# S123X.net
KiCad netlist of a schematic drawn in EAGLE
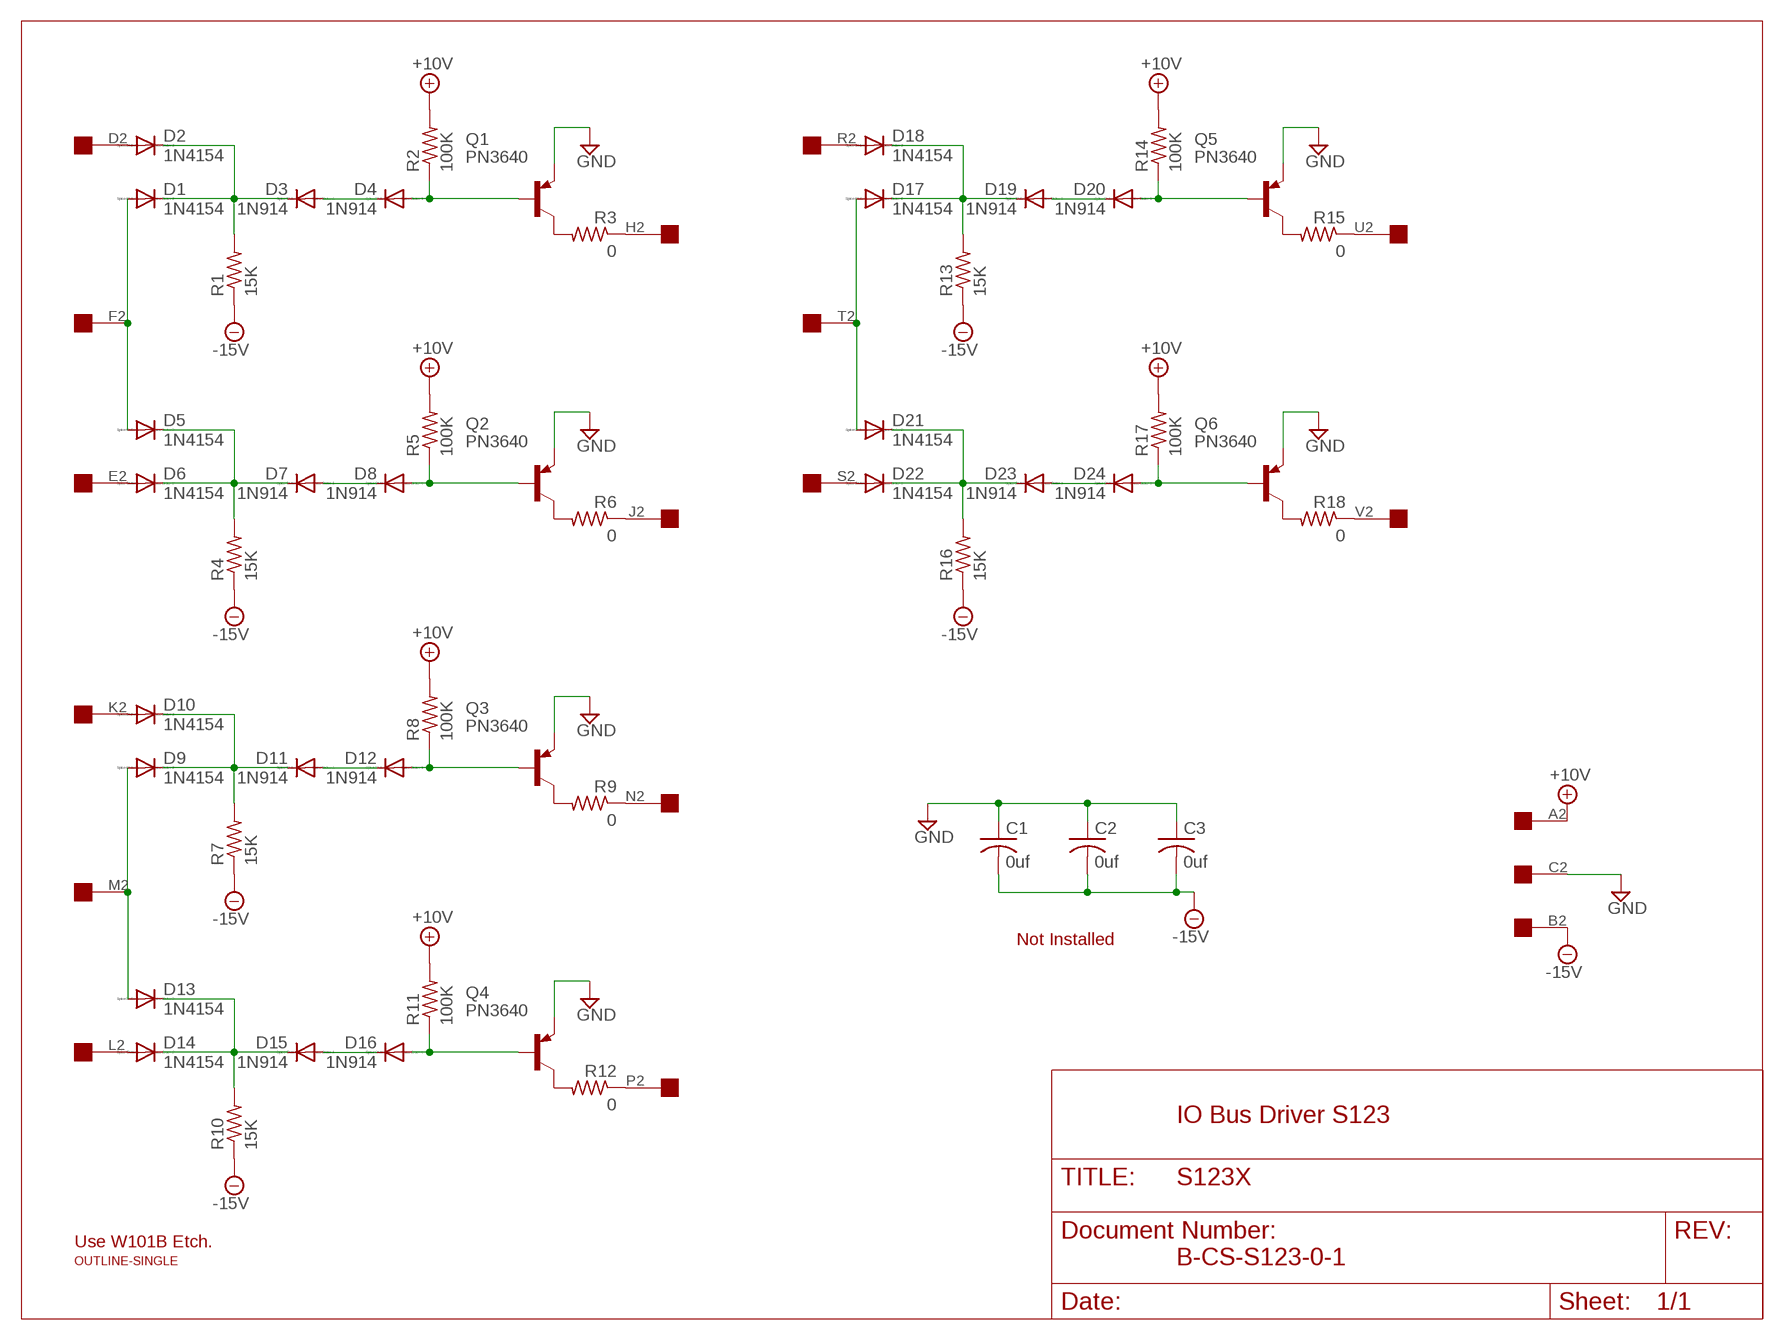
[diagram p0: schematic, sheet 1]

(export (version "E")
  (design (tool "Eeschema 10.0.6"))
  (components
    (comp (ref "C1")
      (value "0uf")
      (footprint "eagle-import:C050-025X075")
      (libsource (lib "eagle-import") (part "C-US050-025X075"))
    )
    (comp (ref "C2")
      (value "0uf")
      (footprint "eagle-import:C050-025X075")
      (libsource (lib "eagle-import") (part "C-US050-025X075"))
    )
    (comp (ref "C3")
      (value "0uf")
      (footprint "eagle-import:C050-025X075")
      (libsource (lib "eagle-import") (part "C-US050-025X075"))
    )
    (comp (ref "D1")
      (value "1N4154")
      (footprint "eagle-import:DO35-10")
      (libsource (lib "eagle-import") (part "1N4148DO35-10"))
    )
    (comp (ref "D2")
      (value "1N4154")
      (footprint "eagle-import:DO35-10")
      (libsource (lib "eagle-import") (part "1N4148DO35-10"))
    )
    (comp (ref "D3")
      (value "1N914")
      (footprint "eagle-import:DO35-10")
      (libsource (lib "eagle-import") (part "1N4148DO35-10"))
    )
    (comp (ref "D4")
      (value "1N914")
      (footprint "eagle-import:DO35-10")
      (libsource (lib "eagle-import") (part "1N4148DO35-10"))
    )
    (comp (ref "D5")
      (value "1N4154")
      (footprint "eagle-import:DO35-10")
      (libsource (lib "eagle-import") (part "1N4148DO35-10"))
    )
    (comp (ref "D6")
      (value "1N4154")
      (footprint "eagle-import:DO35-10")
      (libsource (lib "eagle-import") (part "1N4148DO35-10"))
    )
    (comp (ref "D7")
      (value "1N914")
      (footprint "eagle-import:DO35-10")
      (libsource (lib "eagle-import") (part "1N4148DO35-10"))
    )
    (comp (ref "D8")
      (value "1N914")
      (footprint "eagle-import:DO35-10")
      (libsource (lib "eagle-import") (part "1N4148DO35-10"))
    )
    (comp (ref "D9")
      (value "1N4154")
      (footprint "eagle-import:DO35-10")
      (libsource (lib "eagle-import") (part "1N4148DO35-10"))
    )
    (comp (ref "D10")
      (value "1N4154")
      (footprint "eagle-import:DO35-10")
      (libsource (lib "eagle-import") (part "1N4148DO35-10"))
    )
    (comp (ref "D11")
      (value "1N914")
      (footprint "eagle-import:DO35-10")
      (libsource (lib "eagle-import") (part "1N4148DO35-10"))
    )
    (comp (ref "D12")
      (value "1N914")
      (footprint "eagle-import:DO35-10")
      (libsource (lib "eagle-import") (part "1N4148DO35-10"))
    )
    (comp (ref "D13")
      (value "1N4154")
      (footprint "eagle-import:DO35-10")
      (libsource (lib "eagle-import") (part "1N4148DO35-10"))
    )
    (comp (ref "D14")
      (value "1N4154")
      (footprint "eagle-import:DO35-10")
      (libsource (lib "eagle-import") (part "1N4148DO35-10"))
    )
    (comp (ref "D15")
      (value "1N914")
      (footprint "eagle-import:DO35-10")
      (libsource (lib "eagle-import") (part "1N4148DO35-10"))
    )
    (comp (ref "D16")
      (value "1N914")
      (footprint "eagle-import:DO35-10")
      (libsource (lib "eagle-import") (part "1N4148DO35-10"))
    )
    (comp (ref "D17")
      (value "1N4154")
      (footprint "eagle-import:DO35-10")
      (libsource (lib "eagle-import") (part "1N4148DO35-10"))
    )
    (comp (ref "D18")
      (value "1N4154")
      (footprint "eagle-import:DO35-10")
      (libsource (lib "eagle-import") (part "1N4148DO35-10"))
    )
    (comp (ref "D19")
      (value "1N914")
      (footprint "eagle-import:DO35-10")
      (libsource (lib "eagle-import") (part "1N4148DO35-10"))
    )
    (comp (ref "D20")
      (value "1N914")
      (footprint "eagle-import:DO35-10")
      (libsource (lib "eagle-import") (part "1N4148DO35-10"))
    )
    (comp (ref "D21")
      (value "1N4154")
      (footprint "eagle-import:DO35-10")
      (libsource (lib "eagle-import") (part "1N4148DO35-10"))
    )
    (comp (ref "D22")
      (value "1N4154")
      (footprint "eagle-import:DO35-10")
      (libsource (lib "eagle-import") (part "1N4148DO35-10"))
    )
    (comp (ref "D23")
      (value "1N914")
      (footprint "eagle-import:DO35-10")
      (libsource (lib "eagle-import") (part "1N4148DO35-10"))
    )
    (comp (ref "D24")
      (value "1N914")
      (footprint "eagle-import:DO35-10")
      (libsource (lib "eagle-import") (part "1N4148DO35-10"))
    )
    (comp (ref "Q1")
      (value "PN3640")
      (footprint "eagle-import:TO39")
      (libsource (lib "eagle-import") (part "2N3637"))
    )
    (comp (ref "Q2")
      (value "PN3640")
      (footprint "eagle-import:TO39")
      (libsource (lib "eagle-import") (part "2N3637"))
    )
    (comp (ref "Q3")
      (value "PN3640")
      (footprint "eagle-import:TO39")
      (libsource (lib "eagle-import") (part "2N3637"))
    )
    (comp (ref "Q4")
      (value "PN3640")
      (footprint "eagle-import:TO39")
      (libsource (lib "eagle-import") (part "2N3637"))
    )
    (comp (ref "Q5")
      (value "PN3640")
      (footprint "eagle-import:TO39")
      (libsource (lib "eagle-import") (part "2N3637"))
    )
    (comp (ref "Q6")
      (value "PN3640")
      (footprint "eagle-import:TO39")
      (libsource (lib "eagle-import") (part "2N3637"))
    )
    (comp (ref "R1")
      (value "15K")
      (footprint "eagle-import:0207_10")
      (libsource (lib "eagle-import") (part "R-US_0207/10"))
    )
    (comp (ref "R2")
      (value "100K")
      (footprint "eagle-import:0207_10")
      (libsource (lib "eagle-import") (part "R-US_0207/10"))
    )
    (comp (ref "R3")
      (value "0")
      (footprint "eagle-import:0207_10")
      (libsource (lib "eagle-import") (part "R-US_0207/10"))
    )
    (comp (ref "R4")
      (value "15K")
      (footprint "eagle-import:0207_10")
      (libsource (lib "eagle-import") (part "R-US_0207/10"))
    )
    (comp (ref "R5")
      (value "100K")
      (footprint "eagle-import:0207_10")
      (libsource (lib "eagle-import") (part "R-US_0207/10"))
    )
    (comp (ref "R6")
      (value "0")
      (footprint "eagle-import:0207_10")
      (libsource (lib "eagle-import") (part "R-US_0207/10"))
    )
    (comp (ref "R7")
      (value "15K")
      (footprint "eagle-import:0207_10")
      (libsource (lib "eagle-import") (part "R-US_0207/10"))
    )
    (comp (ref "R8")
      (value "100K")
      (footprint "eagle-import:0207_10")
      (libsource (lib "eagle-import") (part "R-US_0207/10"))
    )
    (comp (ref "R9")
      (value "0")
      (footprint "eagle-import:0207_10")
      (libsource (lib "eagle-import") (part "R-US_0207/10"))
    )
    (comp (ref "R10")
      (value "15K")
      (footprint "eagle-import:0207_10")
      (libsource (lib "eagle-import") (part "R-US_0207/10"))
    )
    (comp (ref "R11")
      (value "100K")
      (footprint "eagle-import:0207_10")
      (libsource (lib "eagle-import") (part "R-US_0207/10"))
    )
    (comp (ref "R12")
      (value "0")
      (footprint "eagle-import:0207_10")
      (libsource (lib "eagle-import") (part "R-US_0207/10"))
    )
    (comp (ref "R13")
      (value "15K")
      (footprint "eagle-import:0207_10")
      (libsource (lib "eagle-import") (part "R-US_0207/10"))
    )
    (comp (ref "R14")
      (value "100K")
      (footprint "eagle-import:0207_10")
      (libsource (lib "eagle-import") (part "R-US_0207/10"))
    )
    (comp (ref "R15")
      (value "0")
      (footprint "eagle-import:0207_10")
      (libsource (lib "eagle-import") (part "R-US_0207/10"))
    )
    (comp (ref "R16")
      (value "15K")
      (footprint "eagle-import:0207_10")
      (libsource (lib "eagle-import") (part "R-US_0207/10"))
    )
    (comp (ref "R17")
      (value "100K")
      (footprint "eagle-import:0207_10")
      (libsource (lib "eagle-import") (part "R-US_0207/10"))
    )
    (comp (ref "R18")
      (value "0")
      (footprint "eagle-import:0207_10")
      (libsource (lib "eagle-import") (part "R-US_0207/10"))
    )
    (comp (ref "U$1")
      (value "OUTLINE-SINGLE")
      (footprint "eagle-import:SINGLE")
      (libsource (lib "eagle-import") (part "OUTLINE-SINGLE"))
    )
    (comp (ref "U$2")
      (value "EDGE-1")
      (footprint "eagle-import:EDGE-CON1")
      (libsource (lib "eagle-import") (part "EDGE-1"))
    )
  )
  (nets
    (net (code "1") (name "+10V") (class "Default")
      (node (ref "R11") (pin "2") (pinfunction "2_2") (pintype "passive"))
      (node (ref "R14") (pin "2") (pinfunction "2_2") (pintype "passive"))
      (node (ref "R17") (pin "2") (pinfunction "2_2") (pintype "passive"))
      (node (ref "R2") (pin "2") (pinfunction "2_2") (pintype "passive"))
      (node (ref "R5") (pin "2") (pinfunction "2_2") (pintype "passive"))
      (node (ref "R8") (pin "2") (pinfunction "2_2") (pintype "passive"))
      (node (ref "U$2") (pin "A2") (pinfunction "1_A2") (pintype "bidirectional"))
    )
    (net (code "2") (name "-15V") (class "Default")
      (node (ref "C1") (pin "2") (pinfunction "2_2") (pintype "passive"))
      (node (ref "C2") (pin "2") (pinfunction "2_2") (pintype "passive"))
      (node (ref "C3") (pin "2") (pinfunction "2_2") (pintype "passive"))
      (node (ref "R1") (pin "1") (pinfunction "1_1") (pintype "passive"))
      (node (ref "R10") (pin "1") (pinfunction "1_1") (pintype "passive"))
      (node (ref "R13") (pin "1") (pinfunction "1_1") (pintype "passive"))
      (node (ref "R16") (pin "1") (pinfunction "1_1") (pintype "passive"))
      (node (ref "R4") (pin "1") (pinfunction "1_1") (pintype "passive"))
      (node (ref "R7") (pin "1") (pinfunction "1_1") (pintype "passive"))
      (node (ref "U$2") (pin "B2") (pinfunction "1_B2") (pintype "bidirectional"))
    )
    (net (code "3") (name "GND") (class "Default")
      (node (ref "C1") (pin "1") (pinfunction "1_1") (pintype "passive"))
      (node (ref "C2") (pin "1") (pinfunction "1_1") (pintype "passive"))
      (node (ref "C3") (pin "1") (pinfunction "1_1") (pintype "passive"))
      (node (ref "Q1") (pin "1") (pinfunction "E_1") (pintype "passive"))
      (node (ref "Q2") (pin "1") (pinfunction "E_1") (pintype "passive"))
      (node (ref "Q3") (pin "1") (pinfunction "E_1") (pintype "passive"))
      (node (ref "Q4") (pin "1") (pinfunction "E_1") (pintype "passive"))
      (node (ref "Q5") (pin "1") (pinfunction "E_1") (pintype "passive"))
      (node (ref "Q6") (pin "1") (pinfunction "E_1") (pintype "passive"))
      (node (ref "U$2") (pin "C2") (pinfunction "1_C2") (pintype "bidirectional"))
    )
    (net (code "4") (name "Net-(D1-PadC)") (class "Default")
      (node (ref "D1") (pin "C") (pinfunction "C_C") (pintype "passive"))
      (node (ref "D2") (pin "C") (pinfunction "C_C") (pintype "passive"))
      (node (ref "D3") (pin "C") (pinfunction "C_C") (pintype "passive"))
      (node (ref "R1") (pin "2") (pinfunction "2_2") (pintype "passive"))
    )
    (net (code "5") (name "Net-(D3-PadA)") (class "Default")
      (node (ref "D3") (pin "A") (pinfunction "A_A") (pintype "passive"))
      (node (ref "D4") (pin "C") (pinfunction "C_C") (pintype "passive"))
    )
    (net (code "6") (name "Net-(D5-PadC)") (class "Default")
      (node (ref "D5") (pin "C") (pinfunction "C_C") (pintype "passive"))
      (node (ref "D6") (pin "C") (pinfunction "C_C") (pintype "passive"))
      (node (ref "D7") (pin "C") (pinfunction "C_C") (pintype "passive"))
      (node (ref "R4") (pin "2") (pinfunction "2_2") (pintype "passive"))
    )
    (net (code "7") (name "Net-(D7-PadA)") (class "Default")
      (node (ref "D7") (pin "A") (pinfunction "A_A") (pintype "passive"))
      (node (ref "D8") (pin "C") (pinfunction "C_C") (pintype "passive"))
    )
    (net (code "8") (name "Net-(D10-PadC)") (class "Default")
      (node (ref "D10") (pin "C") (pinfunction "C_C") (pintype "passive"))
      (node (ref "D11") (pin "C") (pinfunction "C_C") (pintype "passive"))
      (node (ref "D9") (pin "C") (pinfunction "C_C") (pintype "passive"))
      (node (ref "R7") (pin "2") (pinfunction "2_2") (pintype "passive"))
    )
    (net (code "9") (name "Net-(D11-PadA)") (class "Default")
      (node (ref "D11") (pin "A") (pinfunction "A_A") (pintype "passive"))
      (node (ref "D12") (pin "C") (pinfunction "C_C") (pintype "passive"))
    )
    (net (code "10") (name "Net-(D13-PadC)") (class "Default")
      (node (ref "D13") (pin "C") (pinfunction "C_C") (pintype "passive"))
      (node (ref "D14") (pin "C") (pinfunction "C_C") (pintype "passive"))
      (node (ref "D15") (pin "C") (pinfunction "C_C") (pintype "passive"))
      (node (ref "R10") (pin "2") (pinfunction "2_2") (pintype "passive"))
    )
    (net (code "11") (name "Net-(D15-PadA)") (class "Default")
      (node (ref "D15") (pin "A") (pinfunction "A_A") (pintype "passive"))
      (node (ref "D16") (pin "C") (pinfunction "C_C") (pintype "passive"))
    )
    (net (code "12") (name "Net-(D17-PadC)") (class "Default")
      (node (ref "D17") (pin "C") (pinfunction "C_C") (pintype "passive"))
      (node (ref "D18") (pin "C") (pinfunction "C_C") (pintype "passive"))
      (node (ref "D19") (pin "C") (pinfunction "C_C") (pintype "passive"))
      (node (ref "R13") (pin "2") (pinfunction "2_2") (pintype "passive"))
    )
    (net (code "13") (name "Net-(D19-PadA)") (class "Default")
      (node (ref "D19") (pin "A") (pinfunction "A_A") (pintype "passive"))
      (node (ref "D20") (pin "C") (pinfunction "C_C") (pintype "passive"))
    )
    (net (code "14") (name "Net-(D21-PadC)") (class "Default")
      (node (ref "D21") (pin "C") (pinfunction "C_C") (pintype "passive"))
      (node (ref "D22") (pin "C") (pinfunction "C_C") (pintype "passive"))
      (node (ref "D23") (pin "C") (pinfunction "C_C") (pintype "passive"))
      (node (ref "R16") (pin "2") (pinfunction "2_2") (pintype "passive"))
    )
    (net (code "15") (name "Net-(D23-PadA)") (class "Default")
      (node (ref "D23") (pin "A") (pinfunction "A_A") (pintype "passive"))
      (node (ref "D24") (pin "C") (pinfunction "C_C") (pintype "passive"))
    )
    (net (code "16") (name "Net-(Q1-B)") (class "Default")
      (node (ref "D4") (pin "A") (pinfunction "A_A") (pintype "passive"))
      (node (ref "Q1") (pin "2") (pinfunction "B_2") (pintype "passive"))
      (node (ref "R2") (pin "1") (pinfunction "1_1") (pintype "passive"))
    )
    (net (code "17") (name "Net-(Q1-C)") (class "Default")
      (node (ref "Q1") (pin "3") (pinfunction "C_3") (pintype "passive"))
      (node (ref "R3") (pin "2") (pinfunction "2_2") (pintype "passive"))
    )
    (net (code "18") (name "Net-(Q2-B)") (class "Default")
      (node (ref "D8") (pin "A") (pinfunction "A_A") (pintype "passive"))
      (node (ref "Q2") (pin "2") (pinfunction "B_2") (pintype "passive"))
      (node (ref "R5") (pin "1") (pinfunction "1_1") (pintype "passive"))
    )
    (net (code "19") (name "Net-(Q2-C)") (class "Default")
      (node (ref "Q2") (pin "3") (pinfunction "C_3") (pintype "passive"))
      (node (ref "R6") (pin "2") (pinfunction "2_2") (pintype "passive"))
    )
    (net (code "20") (name "Net-(Q3-B)") (class "Default")
      (node (ref "D12") (pin "A") (pinfunction "A_A") (pintype "passive"))
      (node (ref "Q3") (pin "2") (pinfunction "B_2") (pintype "passive"))
      (node (ref "R8") (pin "1") (pinfunction "1_1") (pintype "passive"))
    )
    (net (code "21") (name "Net-(Q3-C)") (class "Default")
      (node (ref "Q3") (pin "3") (pinfunction "C_3") (pintype "passive"))
      (node (ref "R9") (pin "2") (pinfunction "2_2") (pintype "passive"))
    )
    (net (code "22") (name "Net-(Q4-B)") (class "Default")
      (node (ref "D16") (pin "A") (pinfunction "A_A") (pintype "passive"))
      (node (ref "Q4") (pin "2") (pinfunction "B_2") (pintype "passive"))
      (node (ref "R11") (pin "1") (pinfunction "1_1") (pintype "passive"))
    )
    (net (code "23") (name "Net-(Q4-C)") (class "Default")
      (node (ref "Q4") (pin "3") (pinfunction "C_3") (pintype "passive"))
      (node (ref "R12") (pin "2") (pinfunction "2_2") (pintype "passive"))
    )
    (net (code "24") (name "Net-(Q5-B)") (class "Default")
      (node (ref "D20") (pin "A") (pinfunction "A_A") (pintype "passive"))
      (node (ref "Q5") (pin "2") (pinfunction "B_2") (pintype "passive"))
      (node (ref "R14") (pin "1") (pinfunction "1_1") (pintype "passive"))
    )
    (net (code "25") (name "Net-(Q5-C)") (class "Default")
      (node (ref "Q5") (pin "3") (pinfunction "C_3") (pintype "passive"))
      (node (ref "R15") (pin "2") (pinfunction "2_2") (pintype "passive"))
    )
    (net (code "26") (name "Net-(Q6-B)") (class "Default")
      (node (ref "D24") (pin "A") (pinfunction "A_A") (pintype "passive"))
      (node (ref "Q6") (pin "2") (pinfunction "B_2") (pintype "passive"))
      (node (ref "R17") (pin "1") (pinfunction "1_1") (pintype "passive"))
    )
    (net (code "27") (name "Net-(Q6-C)") (class "Default")
      (node (ref "Q6") (pin "3") (pinfunction "C_3") (pintype "passive"))
      (node (ref "R18") (pin "2") (pinfunction "2_2") (pintype "passive"))
    )
    (net (code "28") (name "Net-(U$2D-1)") (class "Default")
      (node (ref "D2") (pin "A") (pinfunction "A_A") (pintype "passive"))
      (node (ref "U$2") (pin "D2") (pinfunction "1_D2") (pintype "bidirectional"))
    )
    (net (code "29") (name "Net-(U$2E-1)") (class "Default")
      (node (ref "D6") (pin "A") (pinfunction "A_A") (pintype "passive"))
      (node (ref "U$2") (pin "E2") (pinfunction "1_E2") (pintype "bidirectional"))
    )
    (net (code "30") (name "Net-(U$2F-1)") (class "Default")
      (node (ref "D1") (pin "A") (pinfunction "A_A") (pintype "passive"))
      (node (ref "D5") (pin "A") (pinfunction "A_A") (pintype "passive"))
      (node (ref "U$2") (pin "F2") (pinfunction "1_F2") (pintype "bidirectional"))
    )
    (net (code "31") (name "Net-(U$2G-1)") (class "Default")
      (node (ref "R3") (pin "1") (pinfunction "1_1") (pintype "passive"))
      (node (ref "U$2") (pin "H2") (pinfunction "1_H2") (pintype "bidirectional"))
    )
    (net (code "32") (name "Net-(U$2H-1)") (class "Default")
      (node (ref "R6") (pin "1") (pinfunction "1_1") (pintype "passive"))
      (node (ref "U$2") (pin "J2") (pinfunction "1_J2") (pintype "bidirectional"))
    )
    (net (code "33") (name "Net-(U$2I-1)") (class "Default")
      (node (ref "D10") (pin "A") (pinfunction "A_A") (pintype "passive"))
      (node (ref "U$2") (pin "K2") (pinfunction "1_K2") (pintype "bidirectional"))
    )
    (net (code "34") (name "Net-(U$2J-1)") (class "Default")
      (node (ref "D14") (pin "A") (pinfunction "A_A") (pintype "passive"))
      (node (ref "U$2") (pin "L2") (pinfunction "1_L2") (pintype "bidirectional"))
    )
    (net (code "35") (name "Net-(U$2K-1)") (class "Default")
      (node (ref "D13") (pin "A") (pinfunction "A_A") (pintype "passive"))
      (node (ref "D9") (pin "A") (pinfunction "A_A") (pintype "passive"))
      (node (ref "U$2") (pin "M2") (pinfunction "1_M2") (pintype "bidirectional"))
    )
    (net (code "36") (name "Net-(U$2L-1)") (class "Default")
      (node (ref "R9") (pin "1") (pinfunction "1_1") (pintype "passive"))
      (node (ref "U$2") (pin "N2") (pinfunction "1_N2") (pintype "bidirectional"))
    )
    (net (code "37") (name "Net-(U$2M-1)") (class "Default")
      (node (ref "R12") (pin "1") (pinfunction "1_1") (pintype "passive"))
      (node (ref "U$2") (pin "P2") (pinfunction "1_P2") (pintype "bidirectional"))
    )
    (net (code "38") (name "Net-(U$2N-1)") (class "Default")
      (node (ref "D18") (pin "A") (pinfunction "A_A") (pintype "passive"))
      (node (ref "U$2") (pin "R2") (pinfunction "1_R2") (pintype "bidirectional"))
    )
    (net (code "39") (name "Net-(U$2O-1)") (class "Default")
      (node (ref "D22") (pin "A") (pinfunction "A_A") (pintype "passive"))
      (node (ref "U$2") (pin "S2") (pinfunction "1_S2") (pintype "bidirectional"))
    )
    (net (code "40") (name "Net-(U$2P-1)") (class "Default")
      (node (ref "D17") (pin "A") (pinfunction "A_A") (pintype "passive"))
      (node (ref "D21") (pin "A") (pinfunction "A_A") (pintype "passive"))
      (node (ref "U$2") (pin "T2") (pinfunction "1_T2") (pintype "bidirectional"))
    )
    (net (code "41") (name "Net-(U$2Q-1)") (class "Default")
      (node (ref "R15") (pin "1") (pinfunction "1_1") (pintype "passive"))
      (node (ref "U$2") (pin "U2") (pinfunction "1_U2") (pintype "bidirectional"))
    )
    (net (code "42") (name "Net-(U$2R-1)") (class "Default")
      (node (ref "R18") (pin "1") (pinfunction "1_1") (pintype "passive"))
      (node (ref "U$2") (pin "V2") (pinfunction "1_V2") (pintype "bidirectional"))
    )
  )
)
